# BOARD.net
KiCad netlist of a schematic drawn in Altium Designer
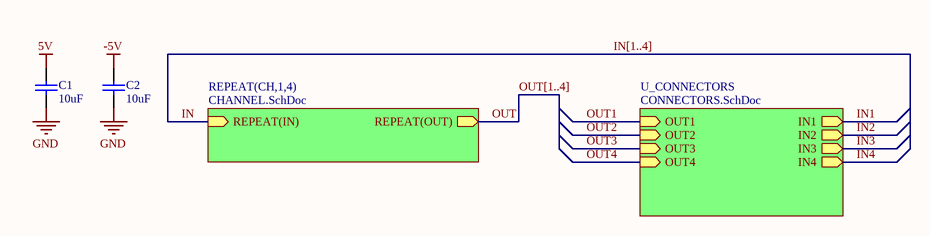
[diagram p0: BOARD.SchDoc]

(export (version "E")
  (design (tool "Eeschema 10.0.6"))
  (components
    (comp (ref "C1")
      (value "10uF")
      (footprint "1608[0603]")
      (description "Capacitor (Semiconductor SIM Model)")
      (fields (field (name "Comment") "Cap Semi") (field (name "PUBLISHER") "Altium Limited"))
      (libsource (lib "Miscellaneous Devices") (part "Cap Semi"))
    )
    (comp (ref "C2")
      (value "10uF")
      (footprint "1608[0603]")
      (description "Capacitor (Semiconductor SIM Model)")
      (fields (field (name "Comment") "Cap Semi") (field (name "PUBLISHER") "Altium Limited"))
      (libsource (lib "Miscellaneous Devices") (part "Cap Semi"))
    )
  )
  (nets
    (net (code "1") (name "-5V") (class "Default")
      (node (ref "C2") (pin "2") (pinfunction "2_2") (pintype "passive"))
    )
    (net (code "14") (name "5V") (class "Default")
      (node (ref "C1") (pin "2") (pinfunction "2_2") (pintype "passive"))
    )
    (net (code "15") (name "GND") (class "Default")
      (node (ref "C1") (pin "1") (pinfunction "1_1") (pintype "passive"))
      (node (ref "C2") (pin "1") (pinfunction "1_1") (pintype "passive"))
    )
  )
)
